# BLE.net
KiCad netlist of a schematic drawn in EAGLE
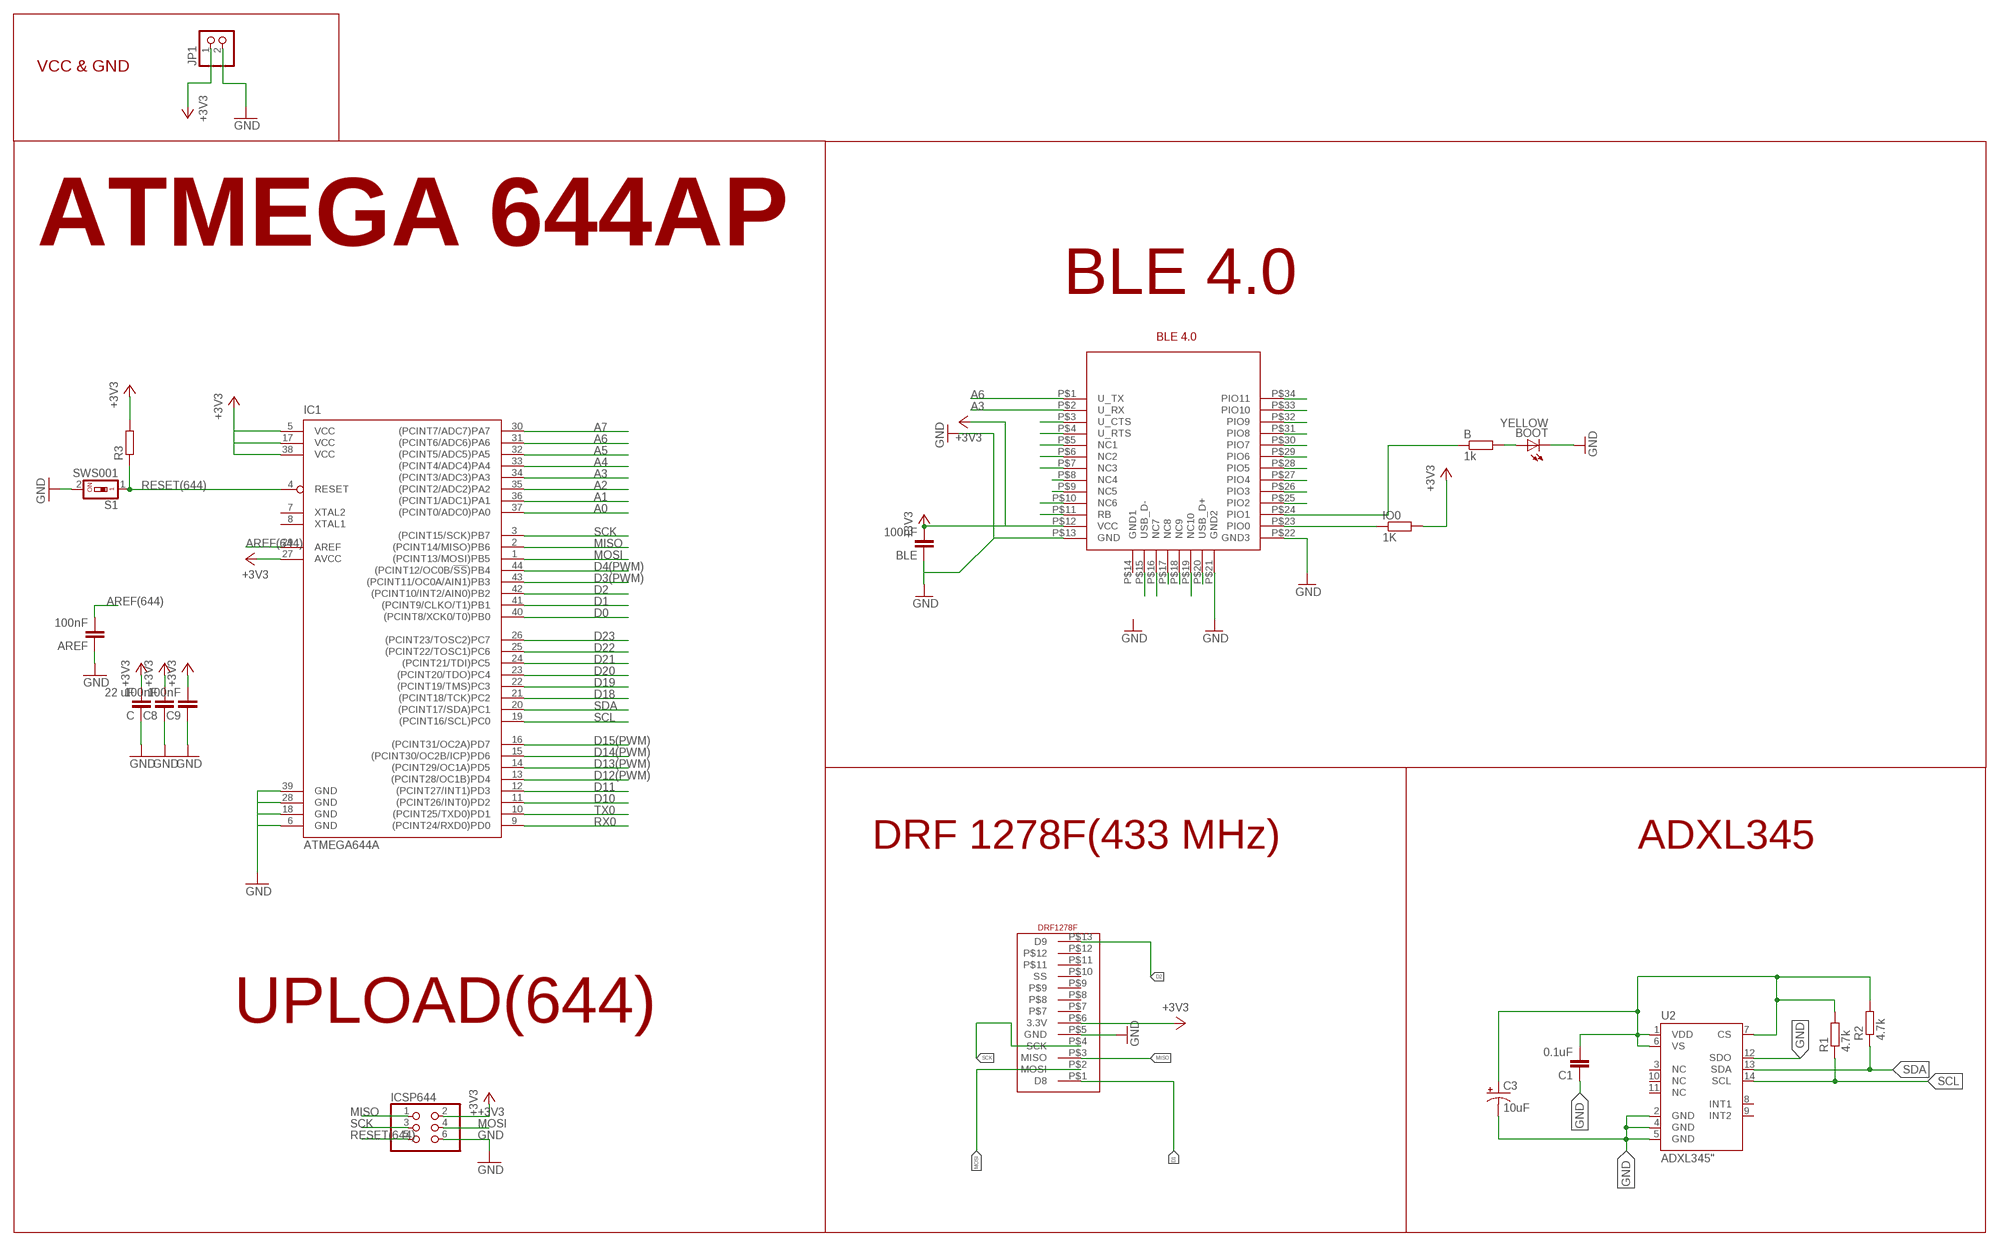
[diagram p0: schematic, sheet 1]

(export (version "E")
  (design (tool "Eeschema 10.0.6"))
  (components
    (comp (ref "AREF")
      (value "100nF")
      (footprint "eagle-import:C0805")
      (libsource (lib "eagle-import") (part "C-EUC0805"))
    )
    (comp (ref "B")
      (value "1k")
      (footprint "eagle-import:R0805")
      (libsource (lib "eagle-import") (part "R-EU_R0805"))
    )
    (comp (ref "BLE")
      (value "100nF")
      (footprint "eagle-import:C0805")
      (libsource (lib "eagle-import") (part "C-EUC0805"))
    )
    (comp (ref "BOOT")
      (value "YELLOW")
      (footprint "eagle-import:CHIP-LED0805")
      (libsource (lib "eagle-import") (part "LEDCHIP-LED0805"))
    )
    (comp (ref "C")
      (value "22 uF")
      (footprint "eagle-import:C0805")
      (libsource (lib "eagle-import") (part "C-EUC0805"))
    )
    (comp (ref "C1")
      (value "0.1uF")
      (footprint "eagle-import:C0805")
      (libsource (lib "eagle-import") (part "C-EUC0805"))
    )
    (comp (ref "C3")
      (value "10uF")
      (footprint "eagle-import:EIA3216")
      (libsource (lib "eagle-import") (part "CAP_POL1206"))
    )
    (comp (ref "C8")
      (value "100nF")
      (footprint "eagle-import:C0805")
      (libsource (lib "eagle-import") (part "C-EUC0805"))
    )
    (comp (ref "C9")
      (value "100nF")
      (footprint "eagle-import:C0805")
      (libsource (lib "eagle-import") (part "C-EUC0805"))
    )
    (comp (ref "IC1")
      (value "ATMEGA644A")
      (footprint "eagle-import:TQFP44")
      (fields (field (name "MPN") "ATMEGA644PV-10AU"))
      (libsource (lib "eagle-import") (part "ATMEGA644A"))
    )
    (comp (ref "ICSP644")
      (value "PINHD-2X3")
      (footprint "eagle-import:2X03")
      (libsource (lib "eagle-import") (part "PINHD-2X3"))
    )
    (comp (ref "IO0")
      (value "1K")
      (footprint "eagle-import:R0805")
      (libsource (lib "eagle-import") (part "R-EU_R0805"))
    )
    (comp (ref "JP1")
      (value "PINHD-1X2")
      (footprint "eagle-import:1X02")
      (libsource (lib "eagle-import") (part "PINHD-1X2"))
    )
    (comp (ref "R1")
      (value "4.7k")
      (footprint "eagle-import:R0805")
      (libsource (lib "eagle-import") (part "R-EU_R0805"))
    )
    (comp (ref "R2")
      (value "4.7k")
      (footprint "eagle-import:R0805")
      (libsource (lib "eagle-import") (part "R-EU_R0805"))
    )
    (comp (ref "R3")
      (value "R-EU_R0805")
      (footprint "eagle-import:R0805")
      (libsource (lib "eagle-import") (part "R-EU_R0805"))
    )
    (comp (ref "S1")
      (value "SWS001")
      (footprint "eagle-import:SMS-001")
      (libsource (lib "eagle-import") (part "SWS001"))
    )
    (comp (ref "U$1")
      (value "DRF1278F")
      (footprint "eagle-import:DIP13")
      (libsource (lib "eagle-import") (part "DRF1278F"))
    )
    (comp (ref "U$6")
      (value "BLUETOOTH_4.0(13)")
      (footprint "eagle-import:BLUTOOTH_4.0(13)")
      (libsource (lib "eagle-import") (part "BLUETOOTH_4.0(13)"))
    )
    (comp (ref "U2")
      (value "ADXL345\"")
      (footprint "eagle-import:ADXL3451_1")
      (libsource (lib "eagle-import") (part "ADXL345{dblquote}"))
    )
  )
  (nets
    (net (code "1") (name "+3V3") (class "Default")
      (node (ref "BLE") (pin "2") (pinfunction "2_2") (pintype "passive"))
      (node (ref "C") (pin "2") (pinfunction "2_2") (pintype "passive"))
      (node (ref "C8") (pin "2") (pinfunction "2_2") (pintype "passive"))
      (node (ref "C9") (pin "2") (pinfunction "2_2") (pintype "passive"))
      (node (ref "IC1") (pin "17") (pinfunction "VCC_17") (pintype "power_in"))
      (node (ref "IC1") (pin "27") (pinfunction "AVCC_27") (pintype "power_in"))
      (node (ref "IC1") (pin "38") (pinfunction "VCC_38") (pintype "power_in"))
      (node (ref "IC1") (pin "5") (pinfunction "VCC_5") (pintype "power_in"))
      (node (ref "ICSP644") (pin "2") (pinfunction "2_2") (pintype "passive"))
      (node (ref "IO0") (pin "2") (pinfunction "2_2") (pintype "passive"))
      (node (ref "JP1") (pin "1") (pinfunction "1_1") (pintype "passive"))
      (node (ref "R3") (pin "2") (pinfunction "2_2") (pintype "passive"))
      (node (ref "U$1") (pin "P$6") (pinfunction "3.3V_P$6") (pintype "bidirectional"))
      (node (ref "U$6") (pin "P$12") (pinfunction "VCC_P$12") (pintype "bidirectional"))
    )
    (net (code "2") (name "/A0") (class "Default")
      (node (ref "IC1") (pin "37") (pinfunction "(PCINT0/ADC0)PA0_37") (pintype "bidirectional"))
    )
    (net (code "3") (name "/A1") (class "Default")
      (node (ref "IC1") (pin "36") (pinfunction "(PCINT1/ADC1)PA1_36") (pintype "bidirectional"))
    )
    (net (code "4") (name "/A2") (class "Default")
      (node (ref "IC1") (pin "35") (pinfunction "(PCINT2/ADC2)PA2_35") (pintype "bidirectional"))
    )
    (net (code "5") (name "/A3") (class "Default")
      (node (ref "IC1") (pin "34") (pinfunction "(PCINT3/ADC3)PA3_34") (pintype "bidirectional"))
      (node (ref "U$6") (pin "P$2") (pinfunction "U_RX_P$2") (pintype "bidirectional"))
    )
    (net (code "6") (name "/A4") (class "Default")
      (node (ref "IC1") (pin "33") (pinfunction "(PCINT4/ADC4)PA4_33") (pintype "bidirectional"))
    )
    (net (code "7") (name "/A5") (class "Default")
      (node (ref "IC1") (pin "32") (pinfunction "(PCINT5/ADC5)PA5_32") (pintype "bidirectional"))
    )
    (net (code "8") (name "/A6") (class "Default")
      (node (ref "IC1") (pin "31") (pinfunction "(PCINT6/ADC6)PA6_31") (pintype "bidirectional"))
      (node (ref "U$6") (pin "P$1") (pinfunction "U_TX_P$1") (pintype "bidirectional"))
    )
    (net (code "9") (name "/A7") (class "Default")
      (node (ref "IC1") (pin "30") (pinfunction "(PCINT7/ADC7)PA7_30") (pintype "bidirectional"))
    )
    (net (code "10") (name "/AREF(644)") (class "Default")
      (node (ref "AREF") (pin "2") (pinfunction "2_2") (pintype "passive"))
      (node (ref "IC1") (pin "29") (pinfunction "AREF_29") (pintype "passive"))
    )
    (net (code "11") (name "/D0") (class "Default")
      (node (ref "IC1") (pin "40") (pinfunction "(PCINT8/XCK0/T0)PB0_40") (pintype "bidirectional"))
    )
    (net (code "12") (name "/D3(PWM)") (class "Default")
      (node (ref "IC1") (pin "43") (pinfunction "(PCINT11/OC0A/AIN1)PB3_43") (pintype "bidirectional"))
    )
    (net (code "13") (name "/D4(PWM)") (class "Default")
      (node (ref "IC1") (pin "44") (pinfunction "(PCINT12/OC0B/~{SS})PB4_44") (pintype "bidirectional"))
    )
    (net (code "14") (name "/D10") (class "Default")
      (node (ref "IC1") (pin "11") (pinfunction "(PCINT26/INT0)PD2_11") (pintype "bidirectional"))
    )
    (net (code "15") (name "/D11") (class "Default")
      (node (ref "IC1") (pin "12") (pinfunction "(PCINT27/INT1)PD3_12") (pintype "bidirectional"))
    )
    (net (code "16") (name "/D12(PWM)") (class "Default")
      (node (ref "IC1") (pin "13") (pinfunction "(PCINT28/OC1B)PD4_13") (pintype "bidirectional"))
    )
    (net (code "17") (name "/D13(PWM)") (class "Default")
      (node (ref "IC1") (pin "14") (pinfunction "(PCINT29/OC1A)PD5_14") (pintype "bidirectional"))
    )
    (net (code "18") (name "/D14(PWM)") (class "Default")
      (node (ref "IC1") (pin "15") (pinfunction "(PCINT30/OC2B/ICP)PD6_15") (pintype "bidirectional"))
    )
    (net (code "19") (name "/D15(PWM)") (class "Default")
      (node (ref "IC1") (pin "16") (pinfunction "(PCINT31/OC2A)PD7_16") (pintype "bidirectional"))
    )
    (net (code "20") (name "/D18") (class "Default")
      (node (ref "IC1") (pin "21") (pinfunction "(PCINT18/TCK)PC2_21") (pintype "output"))
    )
    (net (code "21") (name "/D19") (class "Default")
      (node (ref "IC1") (pin "22") (pinfunction "(PCINT19/TMS)PC3_22") (pintype "output"))
    )
    (net (code "22") (name "/D20") (class "Default")
      (node (ref "IC1") (pin "23") (pinfunction "(PCINT20/TDO)PC4_23") (pintype "output"))
    )
    (net (code "23") (name "/D21") (class "Default")
      (node (ref "IC1") (pin "24") (pinfunction "(PCINT21/TDI)PC5_24") (pintype "output"))
    )
    (net (code "24") (name "/D22") (class "Default")
      (node (ref "IC1") (pin "25") (pinfunction "(PCINT22/TOSC1)PC6_25") (pintype "output"))
    )
    (net (code "25") (name "/D23") (class "Default")
      (node (ref "IC1") (pin "26") (pinfunction "(PCINT23/TOSC2)PC7_26") (pintype "output"))
    )
    (net (code "26") (name "/RESET(644)") (class "Default")
      (node (ref "IC1") (pin "4") (pinfunction "RESET_4") (pintype "input"))
      (node (ref "ICSP644") (pin "5") (pinfunction "5_5") (pintype "passive"))
      (node (ref "R3") (pin "1") (pinfunction "1_1") (pintype "passive"))
      (node (ref "S1") (pin "1") (pinfunction "1_1") (pintype "passive"))
    )
    (net (code "27") (name "/RX0") (class "Default")
      (node (ref "IC1") (pin "9") (pinfunction "(PCINT24/RXD0)PD0_9") (pintype "bidirectional"))
    )
    (net (code "28") (name "/TX0") (class "Default")
      (node (ref "IC1") (pin "10") (pinfunction "(PCINT25/TXD0)PD1_10") (pintype "bidirectional"))
    )
    (net (code "29") (name "D1") (class "Default")
      (node (ref "IC1") (pin "41") (pinfunction "(PCINT9/CLKO/T1)PB1_41") (pintype "bidirectional"))
      (node (ref "U$1") (pin "P$1") (pinfunction "D8_P$1") (pintype "bidirectional"))
    )
    (net (code "30") (name "D2") (class "Default")
      (node (ref "IC1") (pin "42") (pinfunction "(PCINT10/INT2/AIN0)PB2_42") (pintype "bidirectional"))
      (node (ref "U$1") (pin "P$13") (pinfunction "D9_P$13") (pintype "bidirectional"))
    )
    (net (code "31") (name "GND") (class "Default")
      (node (ref "AREF") (pin "1") (pinfunction "1_1") (pintype "passive"))
      (node (ref "BLE") (pin "1") (pinfunction "1_1") (pintype "passive"))
      (node (ref "BOOT") (pin "C") (pinfunction "C_C") (pintype "passive"))
      (node (ref "C") (pin "1") (pinfunction "1_1") (pintype "passive"))
      (node (ref "C1") (pin "1") (pinfunction "1_1") (pintype "passive"))
      (node (ref "C3") (pin "C") (pinfunction "-_C") (pintype "passive"))
      (node (ref "C8") (pin "1") (pinfunction "1_1") (pintype "passive"))
      (node (ref "C9") (pin "1") (pinfunction "1_1") (pintype "passive"))
      (node (ref "IC1") (pin "18") (pinfunction "GND_18") (pintype "power_in"))
      (node (ref "IC1") (pin "28") (pinfunction "GND_28") (pintype "power_in"))
      (node (ref "IC1") (pin "39") (pinfunction "GND_39") (pintype "power_in"))
      (node (ref "IC1") (pin "6") (pinfunction "GND_6") (pintype "power_in"))
      (node (ref "ICSP644") (pin "6") (pinfunction "6_6") (pintype "passive"))
      (node (ref "JP1") (pin "2") (pinfunction "2_2") (pintype "passive"))
      (node (ref "S1") (pin "2") (pinfunction "2_2") (pintype "passive"))
      (node (ref "U$1") (pin "P$5") (pinfunction "GND_P$5") (pintype "bidirectional"))
      (node (ref "U$6") (pin "P$13") (pinfunction "GND_P$13") (pintype "bidirectional"))
      (node (ref "U$6") (pin "P$21") (pinfunction "GND2_P$21") (pintype "bidirectional"))
      (node (ref "U$6") (pin "P$22") (pinfunction "GND3_P$22") (pintype "bidirectional"))
      (node (ref "U2") (pin "12") (pinfunction "SDO_12") (pintype "bidirectional"))
      (node (ref "U2") (pin "2") (pinfunction "GND_2") (pintype "bidirectional"))
      (node (ref "U2") (pin "4") (pinfunction "GND_4") (pintype "bidirectional"))
      (node (ref "U2") (pin "5") (pinfunction "GND_5") (pintype "bidirectional"))
    )
    (net (code "32") (name "MISO") (class "Default")
      (node (ref "IC1") (pin "2") (pinfunction "(PCINT14/MISO)PB6_2") (pintype "bidirectional"))
      (node (ref "ICSP644") (pin "1") (pinfunction "1_1") (pintype "passive"))
      (node (ref "U$1") (pin "P$3") (pinfunction "MISO_P$3") (pintype "bidirectional"))
    )
    (net (code "33") (name "MOSI") (class "Default")
      (node (ref "IC1") (pin "1") (pinfunction "(PCINT13/MOSI)PB5_1") (pintype "bidirectional"))
      (node (ref "ICSP644") (pin "4") (pinfunction "4_4") (pintype "passive"))
      (node (ref "U$1") (pin "P$2") (pinfunction "MOSI_P$2") (pintype "bidirectional"))
    )
    (net (code "34") (name "Net-(B-Pad2)") (class "Default")
      (node (ref "B") (pin "2") (pinfunction "2_2") (pintype "passive"))
      (node (ref "BOOT") (pin "A") (pinfunction "A_A") (pintype "passive"))
    )
    (net (code "35") (name "Net-(C3-+)") (class "Default")
      (node (ref "C1") (pin "2") (pinfunction "2_2") (pintype "passive"))
      (node (ref "C3") (pin "A") (pinfunction "+_A") (pintype "passive"))
      (node (ref "R1") (pin "2") (pinfunction "2_2") (pintype "passive"))
      (node (ref "R2") (pin "2") (pinfunction "2_2") (pintype "passive"))
      (node (ref "U2") (pin "1") (pinfunction "VDD_1") (pintype "bidirectional"))
      (node (ref "U2") (pin "6") (pinfunction "VS_6") (pintype "bidirectional"))
      (node (ref "U2") (pin "7") (pinfunction "CS_7") (pintype "bidirectional"))
    )
    (net (code "36") (name "Net-(U$6-PIO0)") (class "Default")
      (node (ref "IO0") (pin "1") (pinfunction "1_1") (pintype "passive"))
      (node (ref "U$6") (pin "P$23") (pinfunction "PIO0_P$23") (pintype "bidirectional"))
    )
    (net (code "37") (name "Net-(U$6-PIO1)") (class "Default")
      (node (ref "B") (pin "1") (pinfunction "1_1") (pintype "passive"))
      (node (ref "U$6") (pin "P$24") (pinfunction "PIO1_P$24") (pintype "bidirectional"))
    )
    (net (code "38") (name "SCK") (class "Default")
      (node (ref "IC1") (pin "3") (pinfunction "(PCINT15/SCK)PB7_3") (pintype "bidirectional"))
      (node (ref "ICSP644") (pin "3") (pinfunction "3_3") (pintype "passive"))
      (node (ref "U$1") (pin "P$4") (pinfunction "SCK_P$4") (pintype "bidirectional"))
    )
    (net (code "39") (name "SCL") (class "Default")
      (node (ref "IC1") (pin "19") (pinfunction "(PCINT16/SCL)PC0_19") (pintype "output"))
      (node (ref "R1") (pin "1") (pinfunction "1_1") (pintype "passive"))
      (node (ref "U2") (pin "14") (pinfunction "SCL_14") (pintype "bidirectional"))
    )
    (net (code "40") (name "SDA") (class "Default")
      (node (ref "IC1") (pin "20") (pinfunction "(PCINT17/SDA)PC1_20") (pintype "output"))
      (node (ref "R2") (pin "1") (pinfunction "1_1") (pintype "passive"))
      (node (ref "U2") (pin "13") (pinfunction "SDA_13") (pintype "bidirectional"))
    )
    (net (code "41") (name "unconnected-(IC1-XTAL1-Pad8)") (class "Default")
      (node (ref "IC1") (pin "8") (pinfunction "XTAL1_8") (pintype "bidirectional"))
    )
    (net (code "42") (name "unconnected-(IC1-XTAL2-Pad7)") (class "Default")
      (node (ref "IC1") (pin "7") (pinfunction "XTAL2_7") (pintype "bidirectional"))
    )
    (net (code "43") (name "unconnected-(U$1-PadP$7)") (class "Default")
      (node (ref "U$1") (pin "P$7") (pinfunction "P$7_P$7") (pintype "bidirectional"))
    )
    (net (code "44") (name "unconnected-(U$1-PadP$8)") (class "Default")
      (node (ref "U$1") (pin "P$8") (pinfunction "P$8_P$8") (pintype "bidirectional"))
    )
    (net (code "45") (name "unconnected-(U$1-PadP$9)") (class "Default")
      (node (ref "U$1") (pin "P$9") (pinfunction "P$9_P$9") (pintype "bidirectional"))
    )
    (net (code "46") (name "unconnected-(U$1-PadP$11)") (class "Default")
      (node (ref "U$1") (pin "P$11") (pinfunction "P$11_P$11") (pintype "bidirectional"))
    )
    (net (code "47") (name "unconnected-(U$1-PadP$12)") (class "Default")
      (node (ref "U$1") (pin "P$12") (pinfunction "P$12_P$12") (pintype "bidirectional"))
    )
    (net (code "48") (name "unconnected-(U$1-SS-PadP$10)") (class "Default")
      (node (ref "U$1") (pin "P$10") (pinfunction "SS_P$10") (pintype "bidirectional"))
    )
    (net (code "49") (name "unconnected-(U$6-GND1-PadP$14)") (class "Default")
      (node (ref "U$6") (pin "P$14") (pinfunction "GND1_P$14") (pintype "bidirectional"))
    )
    (net (code "50") (name "unconnected-(U$6-NC1-PadP$5)") (class "Default")
      (node (ref "U$6") (pin "P$5") (pinfunction "NC1_P$5") (pintype "bidirectional"))
    )
    (net (code "51") (name "unconnected-(U$6-NC2-PadP$6)") (class "Default")
      (node (ref "U$6") (pin "P$6") (pinfunction "NC2_P$6") (pintype "bidirectional"))
    )
    (net (code "52") (name "unconnected-(U$6-NC3-PadP$7)") (class "Default")
      (node (ref "U$6") (pin "P$7") (pinfunction "NC3_P$7") (pintype "bidirectional"))
    )
    (net (code "53") (name "unconnected-(U$6-NC4-PadP$8)") (class "Default")
      (node (ref "U$6") (pin "P$8") (pinfunction "NC4_P$8") (pintype "bidirectional"))
    )
    (net (code "54") (name "unconnected-(U$6-NC5-PadP$9)") (class "Default")
      (node (ref "U$6") (pin "P$9") (pinfunction "NC5_P$9") (pintype "bidirectional"))
    )
    (net (code "55") (name "unconnected-(U$6-NC6-PadP$10)") (class "Default")
      (node (ref "U$6") (pin "P$10") (pinfunction "NC6_P$10") (pintype "bidirectional"))
    )
    (net (code "56") (name "unconnected-(U$6-NC7-PadP$16)") (class "Default")
      (node (ref "U$6") (pin "P$16") (pinfunction "NC7_P$16") (pintype "bidirectional"))
    )
    (net (code "57") (name "unconnected-(U$6-NC8-PadP$17)") (class "Default")
      (node (ref "U$6") (pin "P$17") (pinfunction "NC8_P$17") (pintype "bidirectional"))
    )
    (net (code "58") (name "unconnected-(U$6-NC9-PadP$18)") (class "Default")
      (node (ref "U$6") (pin "P$18") (pinfunction "NC9_P$18") (pintype "bidirectional"))
    )
    (net (code "59") (name "unconnected-(U$6-NC10-PadP$19)") (class "Default")
      (node (ref "U$6") (pin "P$19") (pinfunction "NC10_P$19") (pintype "bidirectional"))
    )
    (net (code "60") (name "unconnected-(U$6-PIO2-PadP$25)") (class "Default")
      (node (ref "U$6") (pin "P$25") (pinfunction "PIO2_P$25") (pintype "bidirectional"))
    )
    (net (code "61") (name "unconnected-(U$6-PIO3-PadP$26)") (class "Default")
      (node (ref "U$6") (pin "P$26") (pinfunction "PIO3_P$26") (pintype "bidirectional"))
    )
    (net (code "62") (name "unconnected-(U$6-PIO4-PadP$27)") (class "Default")
      (node (ref "U$6") (pin "P$27") (pinfunction "PIO4_P$27") (pintype "bidirectional"))
    )
    (net (code "63") (name "unconnected-(U$6-PIO5-PadP$28)") (class "Default")
      (node (ref "U$6") (pin "P$28") (pinfunction "PIO5_P$28") (pintype "bidirectional"))
    )
    (net (code "64") (name "unconnected-(U$6-PIO6-PadP$29)") (class "Default")
      (node (ref "U$6") (pin "P$29") (pinfunction "PIO6_P$29") (pintype "bidirectional"))
    )
    (net (code "65") (name "unconnected-(U$6-PIO7-PadP$30)") (class "Default")
      (node (ref "U$6") (pin "P$30") (pinfunction "PIO7_P$30") (pintype "bidirectional"))
    )
    (net (code "66") (name "unconnected-(U$6-PIO8-PadP$31)") (class "Default")
      (node (ref "U$6") (pin "P$31") (pinfunction "PIO8_P$31") (pintype "bidirectional"))
    )
    (net (code "67") (name "unconnected-(U$6-PIO9-PadP$32)") (class "Default")
      (node (ref "U$6") (pin "P$32") (pinfunction "PIO9_P$32") (pintype "bidirectional"))
    )
    (net (code "68") (name "unconnected-(U$6-PIO10-PadP$33)") (class "Default")
      (node (ref "U$6") (pin "P$33") (pinfunction "PIO10_P$33") (pintype "bidirectional"))
    )
    (net (code "69") (name "unconnected-(U$6-PIO11-PadP$34)") (class "Default")
      (node (ref "U$6") (pin "P$34") (pinfunction "PIO11_P$34") (pintype "bidirectional"))
    )
    (net (code "70") (name "unconnected-(U$6-RB-PadP$11)") (class "Default")
      (node (ref "U$6") (pin "P$11") (pinfunction "RB_P$11") (pintype "bidirectional"))
    )
    (net (code "71") (name "unconnected-(U$6-USB_D+-PadP$20)") (class "Default")
      (node (ref "U$6") (pin "P$20") (pinfunction "USB_D+_P$20") (pintype "bidirectional"))
    )
    (net (code "72") (name "unconnected-(U$6-USB_D--PadP$15)") (class "Default")
      (node (ref "U$6") (pin "P$15") (pinfunction "USB_D-_P$15") (pintype "bidirectional"))
    )
    (net (code "73") (name "unconnected-(U$6-U_CTS-PadP$3)") (class "Default")
      (node (ref "U$6") (pin "P$3") (pinfunction "U_CTS_P$3") (pintype "bidirectional"))
    )
    (net (code "74") (name "unconnected-(U$6-U_RTS-PadP$4)") (class "Default")
      (node (ref "U$6") (pin "P$4") (pinfunction "U_RTS_P$4") (pintype "bidirectional"))
    )
    (net (code "75") (name "unconnected-(U2-INT1-Pad8)") (class "Default")
      (node (ref "U2") (pin "8") (pinfunction "INT1_8") (pintype "bidirectional"))
    )
    (net (code "76") (name "unconnected-(U2-INT2-Pad9)") (class "Default")
      (node (ref "U2") (pin "9") (pinfunction "INT2_9") (pintype "bidirectional"))
    )
    (net (code "77") (name "unconnected-(U2-NC-Pad3)") (class "Default")
      (node (ref "U2") (pin "3") (pinfunction "NC_3") (pintype "bidirectional"))
    )
    (net (code "78") (name "unconnected-(U2-NC-Pad10)") (class "Default")
      (node (ref "U2") (pin "10") (pinfunction "NC_10") (pintype "bidirectional"))
    )
    (net (code "79") (name "unconnected-(U2-NC-Pad11)") (class "Default")
      (node (ref "U2") (pin "11") (pinfunction "NC_11") (pintype "bidirectional"))
    )
  )
)
